# ADSR1.net
KiCad netlist of a schematic drawn in EAGLE
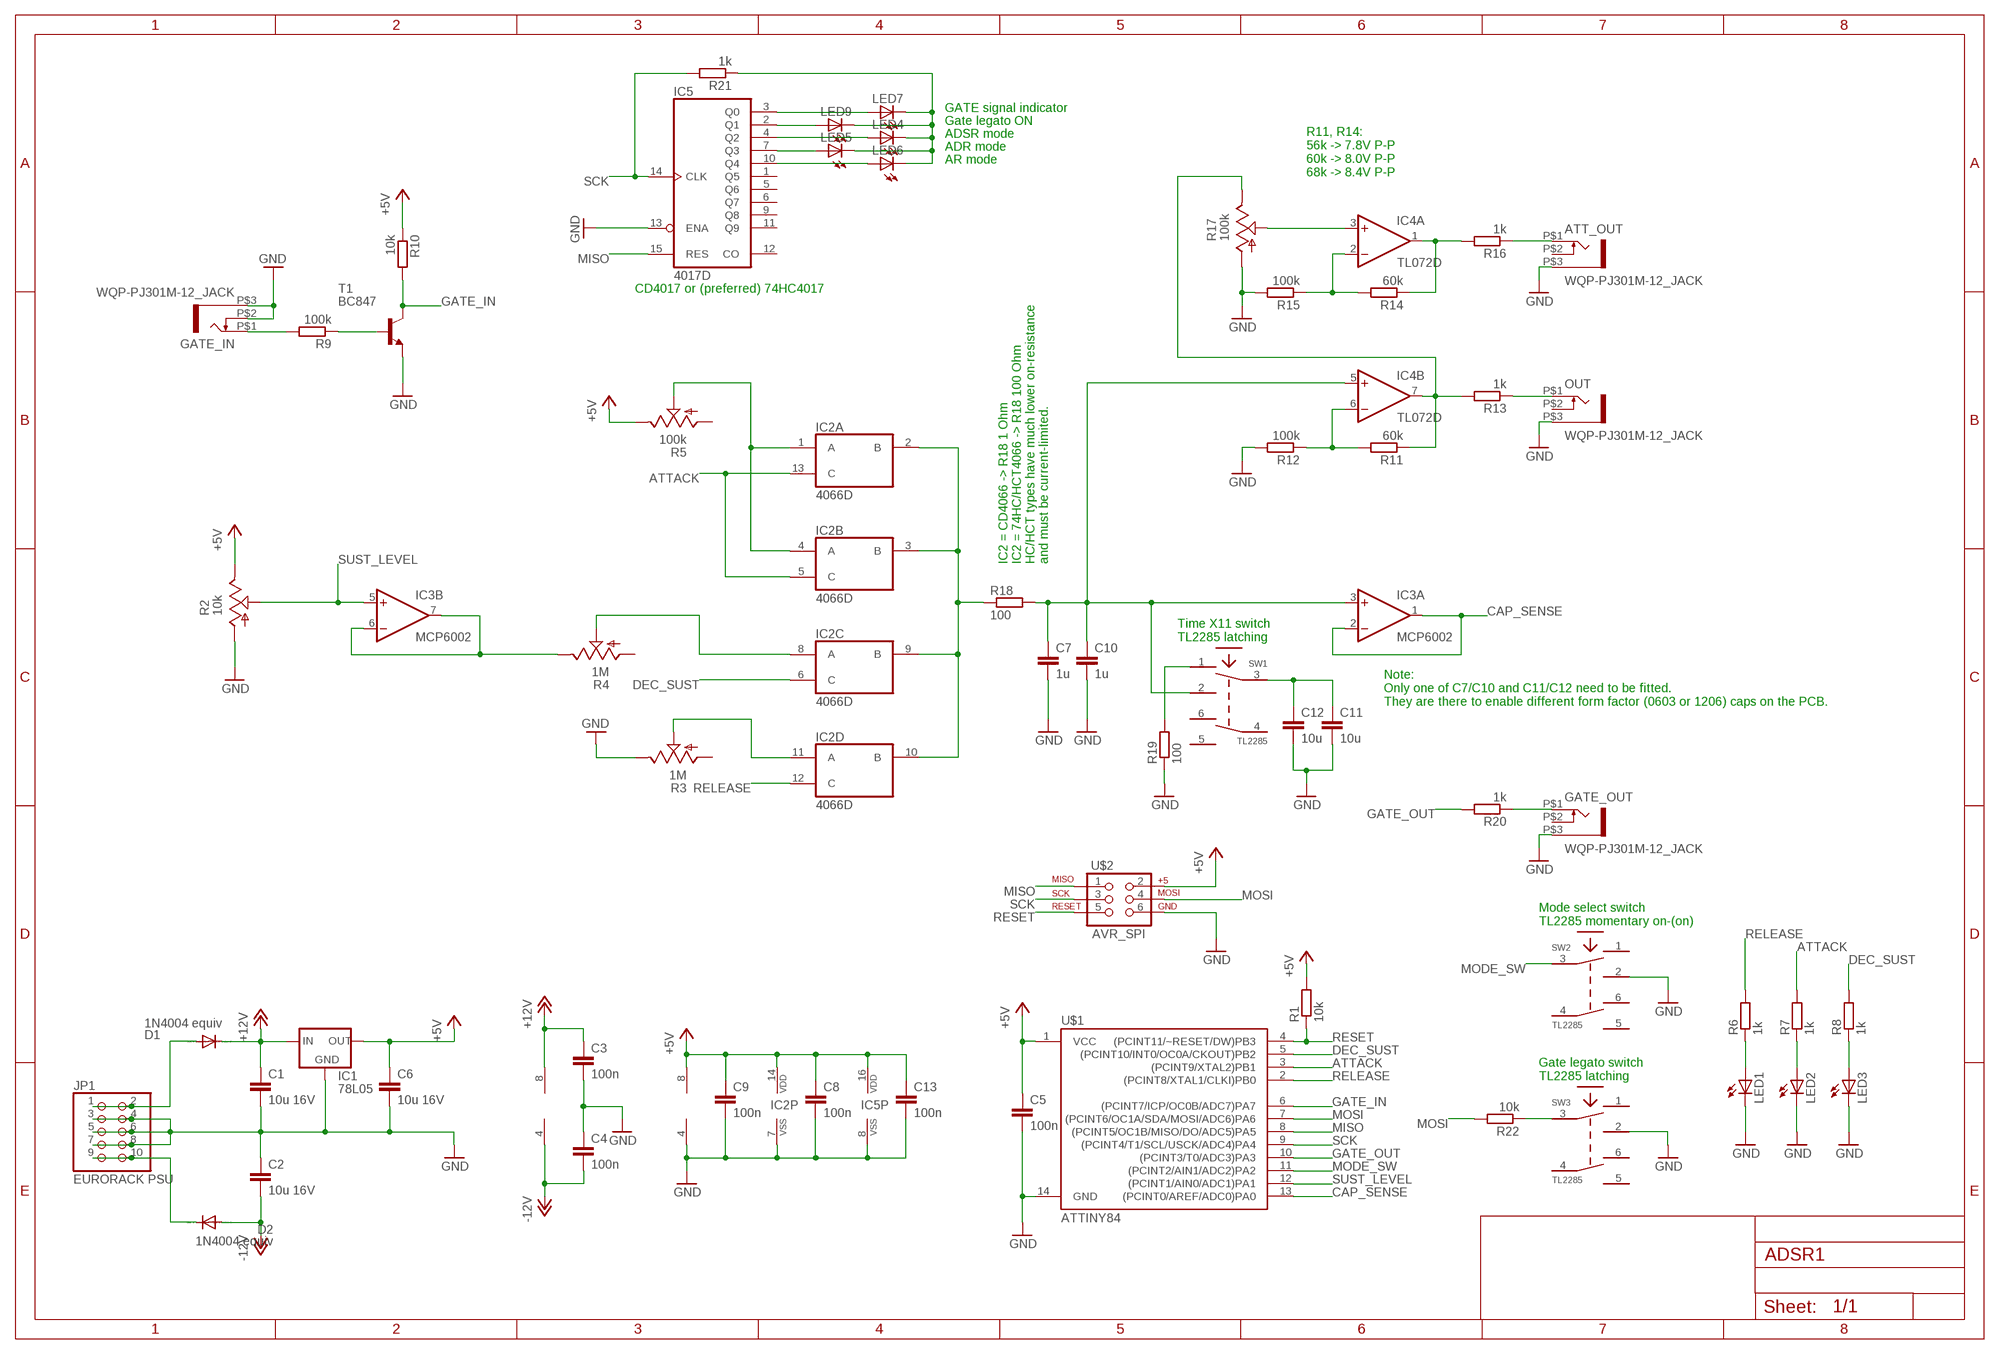
[diagram p0: schematic, sheet 1]

(export (version "E")
  (design (tool "Eeschema 10.0.6"))
  (components
    (comp (ref "ATT_OUT")
      (value "WQP-PJ301M-12_JACK")
      (footprint "eagle-import:WQP-PJ301M-12_JACK")
      (libsource (lib "eagle-import") (part "WQP-PJ301M-12_JACK"))
    )
    (comp (ref "C1")
      (value "10u 16V")
      (footprint "eagle-import:C1206K")
      (libsource (lib "eagle-import") (part "C-EUC1206K"))
    )
    (comp (ref "C2")
      (value "10u 16V")
      (footprint "eagle-import:C1206K")
      (libsource (lib "eagle-import") (part "C-EUC1206K"))
    )
    (comp (ref "C3")
      (value "100n")
      (footprint "eagle-import:C0603K")
      (libsource (lib "eagle-import") (part "C-EUC0603K"))
    )
    (comp (ref "C4")
      (value "100n")
      (footprint "eagle-import:C0603K")
      (libsource (lib "eagle-import") (part "C-EUC0603K"))
    )
    (comp (ref "C5")
      (value "100n")
      (footprint "eagle-import:C0603K")
      (libsource (lib "eagle-import") (part "C-EUC0603K"))
    )
    (comp (ref "C6")
      (value "10u 16V")
      (footprint "eagle-import:C1206K")
      (libsource (lib "eagle-import") (part "C-EUC1206K"))
    )
    (comp (ref "C7")
      (value "1u")
      (footprint "eagle-import:C0603K")
      (libsource (lib "eagle-import") (part "C-EUC0603K"))
    )
    (comp (ref "C8")
      (value "100n")
      (footprint "eagle-import:C0603K")
      (libsource (lib "eagle-import") (part "C-EUC0603K"))
    )
    (comp (ref "C9")
      (value "100n")
      (footprint "eagle-import:C0603K")
      (libsource (lib "eagle-import") (part "C-EUC0603K"))
    )
    (comp (ref "C10")
      (value "1u")
      (footprint "eagle-import:C1206K")
      (libsource (lib "eagle-import") (part "C-EUC1206K"))
    )
    (comp (ref "C11")
      (value "10u")
      (footprint "eagle-import:C1206K")
      (libsource (lib "eagle-import") (part "C-EUC1206K"))
    )
    (comp (ref "C12")
      (value "10u")
      (footprint "eagle-import:C0603K")
      (libsource (lib "eagle-import") (part "C-EUC0603K"))
    )
    (comp (ref "C13")
      (value "100n")
      (footprint "eagle-import:C0603K")
      (libsource (lib "eagle-import") (part "C-EUC0603K"))
    )
    (comp (ref "D1")
      (value "1N4004 equiv")
      (footprint "eagle-import:DO214AA")
      (libsource (lib "eagle-import") (part "DIODE-DO214AA"))
    )
    (comp (ref "D2")
      (value "1N4004 equiv")
      (footprint "eagle-import:DO214AA")
      (libsource (lib "eagle-import") (part "DIODE-DO214AA"))
    )
    (comp (ref "GATE_IN")
      (value "WQP-PJ301M-12_JACK")
      (footprint "eagle-import:WQP-PJ301M-12_JACK")
      (libsource (lib "eagle-import") (part "WQP-PJ301M-12_JACK"))
    )
    (comp (ref "GATE_OUT")
      (value "WQP-PJ301M-12_JACK")
      (footprint "eagle-import:WQP-PJ301M-12_JACK")
      (libsource (lib "eagle-import") (part "WQP-PJ301M-12_JACK"))
    )
    (comp (ref "IC1")
      (value "78L05")
      (footprint "eagle-import:SOT89R")
      (libsource (lib "eagle-import") (part "78LXXSMD"))
    )
    (comp (ref "IC2")
      (value "4066D")
      (footprint "eagle-import:SO14")
      (libsource (lib "eagle-import") (part "4066D"))
    )
    (comp (ref "IC3")
      (value "MCP6002")
      (footprint "eagle-import:SO08")
      (libsource (lib "eagle-import") (part "TL072D"))
    )
    (comp (ref "IC4")
      (value "TL072D")
      (footprint "eagle-import:SO08")
      (libsource (lib "eagle-import") (part "TL072D"))
    )
    (comp (ref "IC5")
      (value "4017D")
      (footprint "eagle-import:SO16")
      (libsource (lib "eagle-import") (part "4017D"))
    )
    (comp (ref "JP1")
      (value "EURORACK PSU")
      (footprint "eagle-import:2X05")
      (libsource (lib "eagle-import") (part "PINHD-2X5"))
    )
    (comp (ref "LED1")
      (value "LED3MM")
      (footprint "eagle-import:LED3MM")
      (libsource (lib "eagle-import") (part "LED3MM"))
    )
    (comp (ref "LED2")
      (value "LED3MM")
      (footprint "eagle-import:LED3MM")
      (libsource (lib "eagle-import") (part "LED3MM"))
    )
    (comp (ref "LED3")
      (value "LED3MM")
      (footprint "eagle-import:LED3MM")
      (libsource (lib "eagle-import") (part "LED3MM"))
    )
    (comp (ref "LED4")
      (value "LED3MM")
      (footprint "eagle-import:LED3MM")
      (libsource (lib "eagle-import") (part "LED3MM"))
    )
    (comp (ref "LED5")
      (value "LED3MM")
      (footprint "eagle-import:LED3MM")
      (libsource (lib "eagle-import") (part "LED3MM"))
    )
    (comp (ref "LED6")
      (value "LED3MM")
      (footprint "eagle-import:LED3MM")
      (libsource (lib "eagle-import") (part "LED3MM"))
    )
    (comp (ref "LED7")
      (value "LED3MM")
      (footprint "eagle-import:LED3MM")
      (libsource (lib "eagle-import") (part "LED3MM"))
    )
    (comp (ref "LED9")
      (value "LED3MM")
      (footprint "eagle-import:LED3MM")
      (libsource (lib "eagle-import") (part "LED3MM"))
    )
    (comp (ref "OUT")
      (value "WQP-PJ301M-12_JACK")
      (footprint "eagle-import:WQP-PJ301M-12_JACK")
      (libsource (lib "eagle-import") (part "WQP-PJ301M-12_JACK"))
    )
    (comp (ref "R1")
      (value "10k")
      (footprint "eagle-import:R0603")
      (libsource (lib "eagle-import") (part "R-EU_R0603"))
    )
    (comp (ref "R2")
      (value "10k")
      (footprint "eagle-import:ALPS_POT_VERTICAL")
      (libsource (lib "eagle-import") (part "POT_USVERTICAL"))
    )
    (comp (ref "R3")
      (value "1M")
      (footprint "eagle-import:ALPS_POT_VERTICAL")
      (libsource (lib "eagle-import") (part "POT_USVERTICAL"))
    )
    (comp (ref "R4")
      (value "1M")
      (footprint "eagle-import:ALPS_POT_VERTICAL")
      (libsource (lib "eagle-import") (part "POT_USVERTICAL"))
    )
    (comp (ref "R5")
      (value "100k")
      (footprint "eagle-import:ALPS_POT_VERTICAL")
      (libsource (lib "eagle-import") (part "POT_USVERTICAL"))
    )
    (comp (ref "R6")
      (value "1k")
      (footprint "eagle-import:R0603")
      (libsource (lib "eagle-import") (part "R-EU_R0603"))
    )
    (comp (ref "R7")
      (value "1k")
      (footprint "eagle-import:R0603")
      (libsource (lib "eagle-import") (part "R-EU_R0603"))
    )
    (comp (ref "R8")
      (value "1k")
      (footprint "eagle-import:R0603")
      (libsource (lib "eagle-import") (part "R-EU_R0603"))
    )
    (comp (ref "R9")
      (value "100k")
      (footprint "eagle-import:R0603")
      (libsource (lib "eagle-import") (part "R-EU_R0603"))
    )
    (comp (ref "R10")
      (value "10k")
      (footprint "eagle-import:R0603")
      (libsource (lib "eagle-import") (part "R-EU_R0603"))
    )
    (comp (ref "R11")
      (value "60k")
      (footprint "eagle-import:R0603")
      (libsource (lib "eagle-import") (part "R-EU_R0603"))
    )
    (comp (ref "R12")
      (value "100k")
      (footprint "eagle-import:R0603")
      (libsource (lib "eagle-import") (part "R-EU_R0603"))
    )
    (comp (ref "R13")
      (value "1k")
      (footprint "eagle-import:R0603")
      (libsource (lib "eagle-import") (part "R-EU_R0603"))
    )
    (comp (ref "R14")
      (value "60k")
      (footprint "eagle-import:R0603")
      (libsource (lib "eagle-import") (part "R-EU_R0603"))
    )
    (comp (ref "R15")
      (value "100k")
      (footprint "eagle-import:R0603")
      (libsource (lib "eagle-import") (part "R-EU_R0603"))
    )
    (comp (ref "R16")
      (value "1k")
      (footprint "eagle-import:R0603")
      (libsource (lib "eagle-import") (part "R-EU_R0603"))
    )
    (comp (ref "R17")
      (value "100k")
      (footprint "eagle-import:ALPS_POT_VERTICAL")
      (libsource (lib "eagle-import") (part "POT_USVERTICAL"))
    )
    (comp (ref "R18")
      (value "100")
      (footprint "eagle-import:R1206")
      (libsource (lib "eagle-import") (part "R-EU_R1206"))
    )
    (comp (ref "R19")
      (value "100")
      (footprint "eagle-import:R1206")
      (libsource (lib "eagle-import") (part "R-EU_R1206"))
    )
    (comp (ref "R20")
      (value "1k")
      (footprint "eagle-import:R0603")
      (libsource (lib "eagle-import") (part "R-EU_R0603"))
    )
    (comp (ref "R21")
      (value "1k")
      (footprint "eagle-import:R0603")
      (libsource (lib "eagle-import") (part "R-EU_R0603"))
    )
    (comp (ref "R22")
      (value "10k")
      (footprint "eagle-import:R0603")
      (libsource (lib "eagle-import") (part "R-EU_R0603"))
    )
    (comp (ref "SW1")
      (value "TL2285")
      (footprint "eagle-import:TL2285_PCB")
      (libsource (lib "eagle-import") (part "TL2285"))
    )
    (comp (ref "SW2")
      (value "TL2285")
      (footprint "eagle-import:TL2285_PCB")
      (libsource (lib "eagle-import") (part "TL2285"))
    )
    (comp (ref "SW3")
      (value "TL2285")
      (footprint "eagle-import:TL2285_PCB")
      (libsource (lib "eagle-import") (part "TL2285"))
    )
    (comp (ref "T1")
      (value "BC847")
      (footprint "eagle-import:SOT23")
      (libsource (lib "eagle-import") (part "BC847"))
    )
    (comp (ref "U$1")
      (value "ATTINY84")
      (footprint "eagle-import:SO14")
      (libsource (lib "eagle-import") (part "ATTINY84"))
    )
    (comp (ref "U$2")
      (value "AVR_SPI")
      (footprint "eagle-import:2X3")
      (libsource (lib "eagle-import") (part "AVR_SPI_PRG_6PTH"))
    )
  )
  (nets
    (net (code "1") (name "+5V") (class "Default")
      (node (ref "C13") (pin "1") (pinfunction "1_1") (pintype "passive"))
      (node (ref "C5") (pin "1") (pinfunction "1_1") (pintype "passive"))
      (node (ref "C6") (pin "1") (pinfunction "1_1") (pintype "passive"))
      (node (ref "C8") (pin "1") (pinfunction "1_1") (pintype "passive"))
      (node (ref "C9") (pin "1") (pinfunction "1_1") (pintype "passive"))
      (node (ref "IC1") (pin "PAD1") (pinfunction "OUT_PAD1") (pintype "passive"))
      (node (ref "IC2") (pin "14") (pinfunction "VDD_14") (pintype "power_in"))
      (node (ref "IC3") (pin "8") (pinfunction "V+_8") (pintype "power_in"))
      (node (ref "IC5") (pin "16") (pinfunction "VDD_16") (pintype "power_in"))
      (node (ref "R1") (pin "2") (pinfunction "2_2") (pintype "passive"))
      (node (ref "R10") (pin "1") (pinfunction "1_1") (pintype "passive"))
      (node (ref "R2") (pin "P$1") (pinfunction "E_P$1") (pintype "passive"))
      (node (ref "R5") (pin "P$1") (pinfunction "E_P$1") (pintype "passive"))
      (node (ref "U$1") (pin "1") (pinfunction "VCC_1") (pintype "bidirectional"))
      (node (ref "U$2") (pin "2") (pinfunction "2_2") (pintype "passive"))
    )
    (net (code "2") (name "+12V") (class "Default")
      (node (ref "C1") (pin "1") (pinfunction "1_1") (pintype "passive"))
      (node (ref "C3") (pin "1") (pinfunction "1_1") (pintype "passive"))
      (node (ref "D1") (pin "C") (pinfunction "C_C") (pintype "passive"))
      (node (ref "IC1") (pin "PAD3") (pinfunction "IN_PAD3") (pintype "input"))
      (node (ref "IC4") (pin "8") (pinfunction "V+_8") (pintype "power_in"))
    )
    (net (code "3") (name "-12V") (class "Default")
      (node (ref "C2") (pin "2") (pinfunction "2_2") (pintype "passive"))
      (node (ref "C4") (pin "2") (pinfunction "2_2") (pintype "passive"))
      (node (ref "D2") (pin "A") (pinfunction "A_A") (pintype "passive"))
      (node (ref "IC4") (pin "4") (pinfunction "V-_4") (pintype "power_in"))
    )
    (net (code "4") (name "/ATTACK") (class "Default")
      (node (ref "IC2") (pin "13") (pinfunction "C_13") (pintype "input"))
      (node (ref "IC2") (pin "5") (pinfunction "C_5") (pintype "input"))
      (node (ref "R7") (pin "2") (pinfunction "2_2") (pintype "passive"))
      (node (ref "U$1") (pin "3") (pinfunction "(PCINT9/XTAL2)PB1_3") (pintype "bidirectional"))
    )
    (net (code "5") (name "/CAP_SENSE") (class "Default")
      (node (ref "IC3") (pin "1") (pinfunction "OUT_1") (pintype "output"))
      (node (ref "IC3") (pin "2") (pinfunction "-IN_2") (pintype "input"))
      (node (ref "U$1") (pin "13") (pinfunction "(PCINT0/AREF/ADC0)PA0_13") (pintype "bidirectional"))
    )
    (net (code "6") (name "/DEC_SUST") (class "Default")
      (node (ref "IC2") (pin "6") (pinfunction "C_6") (pintype "input"))
      (node (ref "R8") (pin "2") (pinfunction "2_2") (pintype "passive"))
      (node (ref "U$1") (pin "5") (pinfunction "(PCINT10/INT0/OC0A/CKOUT)PB2_5") (pintype "bidirectional"))
    )
    (net (code "7") (name "/GATE_IN") (class "Default")
      (node (ref "R10") (pin "2") (pinfunction "2_2") (pintype "passive"))
      (node (ref "T1") (pin "3") (pinfunction "C_3") (pintype "passive"))
      (node (ref "U$1") (pin "6") (pinfunction "(PCINT7/ICP/OC0B/ADC7)PA7_6") (pintype "bidirectional"))
    )
    (net (code "8") (name "/GATE_OUT") (class "Default")
      (node (ref "R20") (pin "2") (pinfunction "2_2") (pintype "passive"))
      (node (ref "U$1") (pin "10") (pinfunction "(PCINT3/T0/ADC3)PA3_10") (pintype "bidirectional"))
    )
    (net (code "9") (name "/MISO") (class "Default")
      (node (ref "IC5") (pin "15") (pinfunction "RES_15") (pintype "input"))
      (node (ref "U$1") (pin "8") (pinfunction "(PCINT5/OC1B/MISO/DO/ADC5)PA5_8") (pintype "bidirectional"))
      (node (ref "U$2") (pin "1") (pinfunction "1_1") (pintype "passive"))
    )
    (net (code "10") (name "/MODE_SW") (class "Default")
      (node (ref "SW2") (pin "3") (pinfunction "P3_3") (pintype "bidirectional"))
      (node (ref "U$1") (pin "11") (pinfunction "(PCINT2/AIN1/ADC2)PA2_11") (pintype "bidirectional"))
    )
    (net (code "11") (name "/MOSI") (class "Default")
      (node (ref "R22") (pin "2") (pinfunction "2_2") (pintype "passive"))
      (node (ref "U$1") (pin "7") (pinfunction "(PCINT6/OC1A/SDA/MOSI/ADC6)PA6_7") (pintype "bidirectional"))
      (node (ref "U$2") (pin "4") (pinfunction "4_4") (pintype "passive"))
    )
    (net (code "12") (name "/RELEASE") (class "Default")
      (node (ref "IC2") (pin "12") (pinfunction "C_12") (pintype "input"))
      (node (ref "R6") (pin "2") (pinfunction "2_2") (pintype "passive"))
      (node (ref "U$1") (pin "2") (pinfunction "(PCINT8/XTAL1/CLKI)PB0_2") (pintype "bidirectional"))
    )
    (net (code "13") (name "/RESET") (class "Default")
      (node (ref "R1") (pin "1") (pinfunction "1_1") (pintype "passive"))
      (node (ref "U$1") (pin "4") (pinfunction "(PCINT11/~{RESET/DW})PB3_4") (pintype "bidirectional"))
      (node (ref "U$2") (pin "5") (pinfunction "5_5") (pintype "passive"))
    )
    (net (code "14") (name "/SCK") (class "Default")
      (node (ref "IC5") (pin "14") (pinfunction "CLK_14") (pintype "input"))
      (node (ref "R21") (pin "2") (pinfunction "2_2") (pintype "passive"))
      (node (ref "U$1") (pin "9") (pinfunction "(PCINT4/T1/SCL/USCK/ADC4)PA4_9") (pintype "bidirectional"))
      (node (ref "U$2") (pin "3") (pinfunction "3_3") (pintype "passive"))
    )
    (net (code "15") (name "/SUST_LEVEL") (class "Default")
      (node (ref "IC3") (pin "5") (pinfunction "+IN_5") (pintype "input"))
      (node (ref "R2") (pin "P$2") (pinfunction "S_P$2") (pintype "passive"))
      (node (ref "U$1") (pin "12") (pinfunction "(PCINT1/AIN0/ADC1)PA1_12") (pintype "bidirectional"))
    )
    (net (code "16") (name "GND") (class "Default")
      (node (ref "ATT_OUT") (pin "P$3") (pinfunction "1_P$3") (pintype "passive"))
      (node (ref "C1") (pin "2") (pinfunction "2_2") (pintype "passive"))
      (node (ref "C10") (pin "2") (pinfunction "2_2") (pintype "passive"))
      (node (ref "C11") (pin "2") (pinfunction "2_2") (pintype "passive"))
      (node (ref "C12") (pin "2") (pinfunction "2_2") (pintype "passive"))
      (node (ref "C13") (pin "2") (pinfunction "2_2") (pintype "passive"))
      (node (ref "C2") (pin "1") (pinfunction "1_1") (pintype "passive"))
      (node (ref "C3") (pin "2") (pinfunction "2_2") (pintype "passive"))
      (node (ref "C4") (pin "1") (pinfunction "1_1") (pintype "passive"))
      (node (ref "C5") (pin "2") (pinfunction "2_2") (pintype "passive"))
      (node (ref "C6") (pin "2") (pinfunction "2_2") (pintype "passive"))
      (node (ref "C7") (pin "2") (pinfunction "2_2") (pintype "passive"))
      (node (ref "C8") (pin "2") (pinfunction "2_2") (pintype "passive"))
      (node (ref "C9") (pin "2") (pinfunction "2_2") (pintype "passive"))
      (node (ref "GATE_IN") (pin "P$2") (pinfunction "3_P$2") (pintype "passive"))
      (node (ref "GATE_IN") (pin "P$3") (pinfunction "1_P$3") (pintype "passive"))
      (node (ref "GATE_OUT") (pin "P$3") (pinfunction "1_P$3") (pintype "passive"))
      (node (ref "IC1") (pin "PAD2") (pinfunction "GND_PAD2") (pintype "input"))
      (node (ref "IC1") (pin "PAD4") (pinfunction "GND_PAD4") (pintype "input"))
      (node (ref "IC2") (pin "7") (pinfunction "VSS_7") (pintype "power_in"))
      (node (ref "IC3") (pin "4") (pinfunction "V-_4") (pintype "power_in"))
      (node (ref "IC5") (pin "13") (pinfunction "ENA_13") (pintype "input"))
      (node (ref "IC5") (pin "8") (pinfunction "VSS_8") (pintype "power_in"))
      (node (ref "JP1") (pin "3") (pinfunction "3_3") (pintype "passive"))
      (node (ref "JP1") (pin "4") (pinfunction "4_4") (pintype "passive"))
      (node (ref "JP1") (pin "5") (pinfunction "5_5") (pintype "passive"))
      (node (ref "JP1") (pin "6") (pinfunction "6_6") (pintype "passive"))
      (node (ref "JP1") (pin "7") (pinfunction "7_7") (pintype "passive"))
      (node (ref "JP1") (pin "8") (pinfunction "8_8") (pintype "passive"))
      (node (ref "LED1") (pin "K") (pinfunction "C_K") (pintype "passive"))
      (node (ref "LED2") (pin "K") (pinfunction "C_K") (pintype "passive"))
      (node (ref "LED3") (pin "K") (pinfunction "C_K") (pintype "passive"))
      (node (ref "OUT") (pin "P$3") (pinfunction "1_P$3") (pintype "passive"))
      (node (ref "R12") (pin "2") (pinfunction "2_2") (pintype "passive"))
      (node (ref "R15") (pin "2") (pinfunction "2_2") (pintype "passive"))
      (node (ref "R17") (pin "P$3") (pinfunction "A_P$3") (pintype "passive"))
      (node (ref "R19") (pin "1") (pinfunction "1_1") (pintype "passive"))
      (node (ref "R2") (pin "P$3") (pinfunction "A_P$3") (pintype "passive"))
      (node (ref "R3") (pin "P$1") (pinfunction "E_P$1") (pintype "passive"))
      (node (ref "SW2") (pin "2") (pinfunction "P2_2") (pintype "bidirectional"))
      (node (ref "SW3") (pin "2") (pinfunction "P2_2") (pintype "bidirectional"))
      (node (ref "T1") (pin "2") (pinfunction "E_2") (pintype "passive"))
      (node (ref "U$1") (pin "14") (pinfunction "GND_14") (pintype "bidirectional"))
      (node (ref "U$2") (pin "6") (pinfunction "6_6") (pintype "passive"))
    )
    (net (code "17") (name "Net-(ATT_OUT-2)") (class "Default")
      (node (ref "ATT_OUT") (pin "P$1") (pinfunction "2_P$1") (pintype "passive"))
      (node (ref "R16") (pin "1") (pinfunction "1_1") (pintype "passive"))
    )
    (net (code "18") (name "Net-(D1-PadA)") (class "Default")
      (node (ref "D1") (pin "A") (pinfunction "A_A") (pintype "passive"))
      (node (ref "JP1") (pin "1") (pinfunction "1_1") (pintype "passive"))
      (node (ref "JP1") (pin "2") (pinfunction "2_2") (pintype "passive"))
    )
    (net (code "19") (name "Net-(D2-PadC)") (class "Default")
      (node (ref "D2") (pin "C") (pinfunction "C_C") (pintype "passive"))
      (node (ref "JP1") (pin "10") (pinfunction "10_10") (pintype "passive"))
      (node (ref "JP1") (pin "9") (pinfunction "9_9") (pintype "passive"))
    )
    (net (code "20") (name "Net-(GATE_IN-2)") (class "Default")
      (node (ref "GATE_IN") (pin "P$1") (pinfunction "2_P$1") (pintype "passive"))
      (node (ref "R9") (pin "2") (pinfunction "2_2") (pintype "passive"))
    )
    (net (code "21") (name "Net-(GATE_OUT-2)") (class "Default")
      (node (ref "GATE_OUT") (pin "P$1") (pinfunction "2_P$1") (pintype "passive"))
      (node (ref "R20") (pin "1") (pinfunction "1_1") (pintype "passive"))
    )
    (net (code "22") (name "Net-(IC2A-A)") (class "Default")
      (node (ref "IC2") (pin "1") (pinfunction "A_1") (pintype "tri_state"))
      (node (ref "IC2") (pin "4") (pinfunction "A_4") (pintype "tri_state"))
      (node (ref "R5") (pin "P$2") (pinfunction "S_P$2") (pintype "passive"))
    )
    (net (code "23") (name "Net-(IC2A-B)") (class "Default")
      (node (ref "IC2") (pin "10") (pinfunction "B_10") (pintype "tri_state"))
      (node (ref "IC2") (pin "2") (pinfunction "B_2") (pintype "tri_state"))
      (node (ref "IC2") (pin "3") (pinfunction "B_3") (pintype "tri_state"))
      (node (ref "IC2") (pin "9") (pinfunction "B_9") (pintype "tri_state"))
      (node (ref "R18") (pin "1") (pinfunction "1_1") (pintype "passive"))
    )
    (net (code "24") (name "Net-(IC2C-A)") (class "Default")
      (node (ref "IC2") (pin "8") (pinfunction "A_8") (pintype "tri_state"))
      (node (ref "R4") (pin "P$2") (pinfunction "S_P$2") (pintype "passive"))
    )
    (net (code "25") (name "Net-(IC2D-A)") (class "Default")
      (node (ref "IC2") (pin "11") (pinfunction "A_11") (pintype "tri_state"))
      (node (ref "R3") (pin "P$2") (pinfunction "S_P$2") (pintype "passive"))
    )
    (net (code "26") (name "Net-(IC3A-+IN)") (class "Default")
      (node (ref "C10") (pin "1") (pinfunction "1_1") (pintype "passive"))
      (node (ref "C7") (pin "1") (pinfunction "1_1") (pintype "passive"))
      (node (ref "IC3") (pin "3") (pinfunction "+IN_3") (pintype "input"))
      (node (ref "IC4") (pin "5") (pinfunction "+IN_5") (pintype "input"))
      (node (ref "R18") (pin "2") (pinfunction "2_2") (pintype "passive"))
      (node (ref "SW1") (pin "2") (pinfunction "P2_2") (pintype "bidirectional"))
    )
    (net (code "27") (name "Net-(IC3B--IN)") (class "Default")
      (node (ref "IC3") (pin "6") (pinfunction "-IN_6") (pintype "input"))
      (node (ref "IC3") (pin "7") (pinfunction "OUT_7") (pintype "output"))
      (node (ref "R4") (pin "P$1") (pinfunction "E_P$1") (pintype "passive"))
    )
    (net (code "28") (name "Net-(IC4A-+IN)") (class "Default")
      (node (ref "IC4") (pin "3") (pinfunction "+IN_3") (pintype "input"))
      (node (ref "R17") (pin "P$2") (pinfunction "S_P$2") (pintype "passive"))
    )
    (net (code "29") (name "Net-(IC4A--IN)") (class "Default")
      (node (ref "IC4") (pin "2") (pinfunction "-IN_2") (pintype "input"))
      (node (ref "R14") (pin "2") (pinfunction "2_2") (pintype "passive"))
      (node (ref "R15") (pin "1") (pinfunction "1_1") (pintype "passive"))
    )
    (net (code "30") (name "Net-(IC4A-OUT)") (class "Default")
      (node (ref "IC4") (pin "1") (pinfunction "OUT_1") (pintype "output"))
      (node (ref "R14") (pin "1") (pinfunction "1_1") (pintype "passive"))
      (node (ref "R16") (pin "2") (pinfunction "2_2") (pintype "passive"))
    )
    (net (code "31") (name "Net-(IC4B--IN)") (class "Default")
      (node (ref "IC4") (pin "6") (pinfunction "-IN_6") (pintype "input"))
      (node (ref "R11") (pin "2") (pinfunction "2_2") (pintype "passive"))
      (node (ref "R12") (pin "1") (pinfunction "1_1") (pintype "passive"))
    )
    (net (code "32") (name "Net-(IC4B-OUT)") (class "Default")
      (node (ref "IC4") (pin "7") (pinfunction "OUT_7") (pintype "output"))
      (node (ref "R11") (pin "1") (pinfunction "1_1") (pintype "passive"))
      (node (ref "R13") (pin "2") (pinfunction "2_2") (pintype "passive"))
      (node (ref "R17") (pin "P$1") (pinfunction "E_P$1") (pintype "passive"))
    )
    (net (code "33") (name "Net-(IC5A-Q0)") (class "Default")
      (node (ref "IC5") (pin "3") (pinfunction "Q0_3") (pintype "output"))
      (node (ref "LED7") (pin "A") (pinfunction "A_A") (pintype "passive"))
    )
    (net (code "34") (name "Net-(IC5A-Q1)") (class "Default")
      (node (ref "IC5") (pin "2") (pinfunction "Q1_2") (pintype "output"))
      (node (ref "LED9") (pin "A") (pinfunction "A_A") (pintype "passive"))
    )
    (net (code "35") (name "Net-(IC5A-Q2)") (class "Default")
      (node (ref "IC5") (pin "4") (pinfunction "Q2_4") (pintype "output"))
      (node (ref "LED4") (pin "A") (pinfunction "A_A") (pintype "passive"))
    )
    (net (code "36") (name "Net-(IC5A-Q3)") (class "Default")
      (node (ref "IC5") (pin "7") (pinfunction "Q3_7") (pintype "output"))
      (node (ref "LED5") (pin "A") (pinfunction "A_A") (pintype "passive"))
    )
    (net (code "37") (name "Net-(IC5A-Q4)") (class "Default")
      (node (ref "IC5") (pin "10") (pinfunction "Q4_10") (pintype "output"))
      (node (ref "LED6") (pin "A") (pinfunction "A_A") (pintype "passive"))
    )
    (net (code "38") (name "Net-(LED1-PadA)") (class "Default")
      (node (ref "LED1") (pin "A") (pinfunction "A_A") (pintype "passive"))
      (node (ref "R6") (pin "1") (pinfunction "1_1") (pintype "passive"))
    )
    (net (code "39") (name "Net-(LED2-PadA)") (class "Default")
      (node (ref "LED2") (pin "A") (pinfunction "A_A") (pintype "passive"))
      (node (ref "R7") (pin "1") (pinfunction "1_1") (pintype "passive"))
    )
    (net (code "40") (name "Net-(LED3-PadA)") (class "Default")
      (node (ref "LED3") (pin "A") (pinfunction "A_A") (pintype "passive"))
      (node (ref "R8") (pin "1") (pinfunction "1_1") (pintype "passive"))
    )
    (net (code "41") (name "Net-(LED4-C)") (class "Default")
      (node (ref "LED4") (pin "K") (pinfunction "C_K") (pintype "passive"))
      (node (ref "LED5") (pin "K") (pinfunction "C_K") (pintype "passive"))
      (node (ref "LED6") (pin "K") (pinfunction "C_K") (pintype "passive"))
      (node (ref "LED7") (pin "K") (pinfunction "C_K") (pintype "passive"))
      (node (ref "LED9") (pin "K") (pinfunction "C_K") (pintype "passive"))
      (node (ref "R21") (pin "1") (pinfunction "1_1") (pintype "passive"))
    )
    (net (code "42") (name "Net-(OUT-2)") (class "Default")
      (node (ref "OUT") (pin "P$1") (pinfunction "2_P$1") (pintype "passive"))
      (node (ref "R13") (pin "1") (pinfunction "1_1") (pintype "passive"))
    )
    (net (code "43") (name "Net-(SW1-P1)") (class "Default")
      (node (ref "R19") (pin "2") (pinfunction "2_2") (pintype "passive"))
      (node (ref "SW1") (pin "1") (pinfunction "P1_1") (pintype "bidirectional"))
    )
    (net (code "44") (name "Net-(SW1-P3)") (class "Default")
      (node (ref "C11") (pin "1") (pinfunction "1_1") (pintype "passive"))
      (node (ref "C12") (pin "1") (pinfunction "1_1") (pintype "passive"))
      (node (ref "SW1") (pin "3") (pinfunction "P3_3") (pintype "bidirectional"))
    )
    (net (code "45") (name "Net-(SW3-P3)") (class "Default")
      (node (ref "R22") (pin "1") (pinfunction "1_1") (pintype "passive"))
      (node (ref "SW3") (pin "3") (pinfunction "P3_3") (pintype "bidirectional"))
    )
    (net (code "46") (name "Net-(T1-B)") (class "Default")
      (node (ref "R9") (pin "1") (pinfunction "1_1") (pintype "passive"))
      (node (ref "T1") (pin "1") (pinfunction "B_1") (pintype "passive"))
    )
    (net (code "47") (name "unconnected-(ATT_OUT-3-PadP$2)") (class "Default")
      (node (ref "ATT_OUT") (pin "P$2") (pinfunction "3_P$2") (pintype "passive"))
    )
    (net (code "48") (name "unconnected-(GATE_OUT-3-PadP$2)") (class "Default")
      (node (ref "GATE_OUT") (pin "P$2") (pinfunction "3_P$2") (pintype "passive"))
    )
    (net (code "49") (name "unconnected-(IC5A-CO-Pad12)") (class "Default")
      (node (ref "IC5") (pin "12") (pinfunction "CO_12") (pintype "output"))
    )
    (net (code "50") (name "unconnected-(IC5A-Q5-Pad1)") (class "Default")
      (node (ref "IC5") (pin "1") (pinfunction "Q5_1") (pintype "output"))
    )
    (net (code "51") (name "unconnected-(IC5A-Q6-Pad5)") (class "Default")
      (node (ref "IC5") (pin "5") (pinfunction "Q6_5") (pintype "output"))
    )
    (net (code "52") (name "unconnected-(IC5A-Q7-Pad6)") (class "Default")
      (node (ref "IC5") (pin "6") (pinfunction "Q7_6") (pintype "output"))
    )
    (net (code "53") (name "unconnected-(IC5A-Q8-Pad9)") (class "Default")
      (node (ref "IC5") (pin "9") (pinfunction "Q8_9") (pintype "output"))
    )
    (net (code "54") (name "unconnected-(IC5A-Q9-Pad11)") (class "Default")
      (node (ref "IC5") (pin "11") (pinfunction "Q9_11") (pintype "output"))
    )
    (net (code "55") (name "unconnected-(OUT-3-PadP$2)") (class "Default")
      (node (ref "OUT") (pin "P$2") (pinfunction "3_P$2") (pintype "passive"))
    )
    (net (code "56") (name "unconnected-(R3-A-PadP$3)") (class "Default")
      (node (ref "R3") (pin "P$3") (pinfunction "A_P$3") (pintype "passive"))
    )
    (net (code "57") (name "unconnected-(R4-A-PadP$3)") (class "Default")
      (node (ref "R4") (pin "P$3") (pinfunction "A_P$3") (pintype "passive"))
    )
    (net (code "58") (name "unconnected-(R5-A-PadP$3)") (class "Default")
      (node (ref "R5") (pin "P$3") (pinfunction "A_P$3") (pintype "passive"))
    )
    (net (code "59") (name "unconnected-(SW1-P4-Pad4)") (class "Default")
      (node (ref "SW1") (pin "4") (pinfunction "P4_4") (pintype "bidirectional"))
    )
    (net (code "60") (name "unconnected-(SW1-P5-Pad5)") (class "Default")
      (node (ref "SW1") (pin "5") (pinfunction "P5_5") (pintype "bidirectional"))
    )
    (net (code "61") (name "unconnected-(SW1-P6-Pad6)") (class "Default")
      (node (ref "SW1") (pin "6") (pinfunction "P6_6") (pintype "bidirectional"))
    )
    (net (code "62") (name "unconnected-(SW2-P1-Pad1)") (class "Default")
      (node (ref "SW2") (pin "1") (pinfunction "P1_1") (pintype "bidirectional"))
    )
    (net (code "63") (name "unconnected-(SW2-P4-Pad4)") (class "Default")
      (node (ref "SW2") (pin "4") (pinfunction "P4_4") (pintype "bidirectional"))
    )
    (net (code "64") (name "unconnected-(SW2-P5-Pad5)") (class "Default")
      (node (ref "SW2") (pin "5") (pinfunction "P5_5") (pintype "bidirectional"))
    )
    (net (code "65") (name "unconnected-(SW2-P6-Pad6)") (class "Default")
      (node (ref "SW2") (pin "6") (pinfunction "P6_6") (pintype "bidirectional"))
    )
    (net (code "66") (name "unconnected-(SW3-P1-Pad1)") (class "Default")
      (node (ref "SW3") (pin "1") (pinfunction "P1_1") (pintype "bidirectional"))
    )
    (net (code "67") (name "unconnected-(SW3-P4-Pad4)") (class "Default")
      (node (ref "SW3") (pin "4") (pinfunction "P4_4") (pintype "bidirectional"))
    )
    (net (code "68") (name "unconnected-(SW3-P5-Pad5)") (class "Default")
      (node (ref "SW3") (pin "5") (pinfunction "P5_5") (pintype "bidirectional"))
    )
    (net (code "69") (name "unconnected-(SW3-P6-Pad6)") (class "Default")
      (node (ref "SW3") (pin "6") (pinfunction "P6_6") (pintype "bidirectional"))
    )
  )
)
